# MAZ000159_-_Diagrama_el_ctrico.net
KiCad netlist of a schematic drawn in Altium Designer
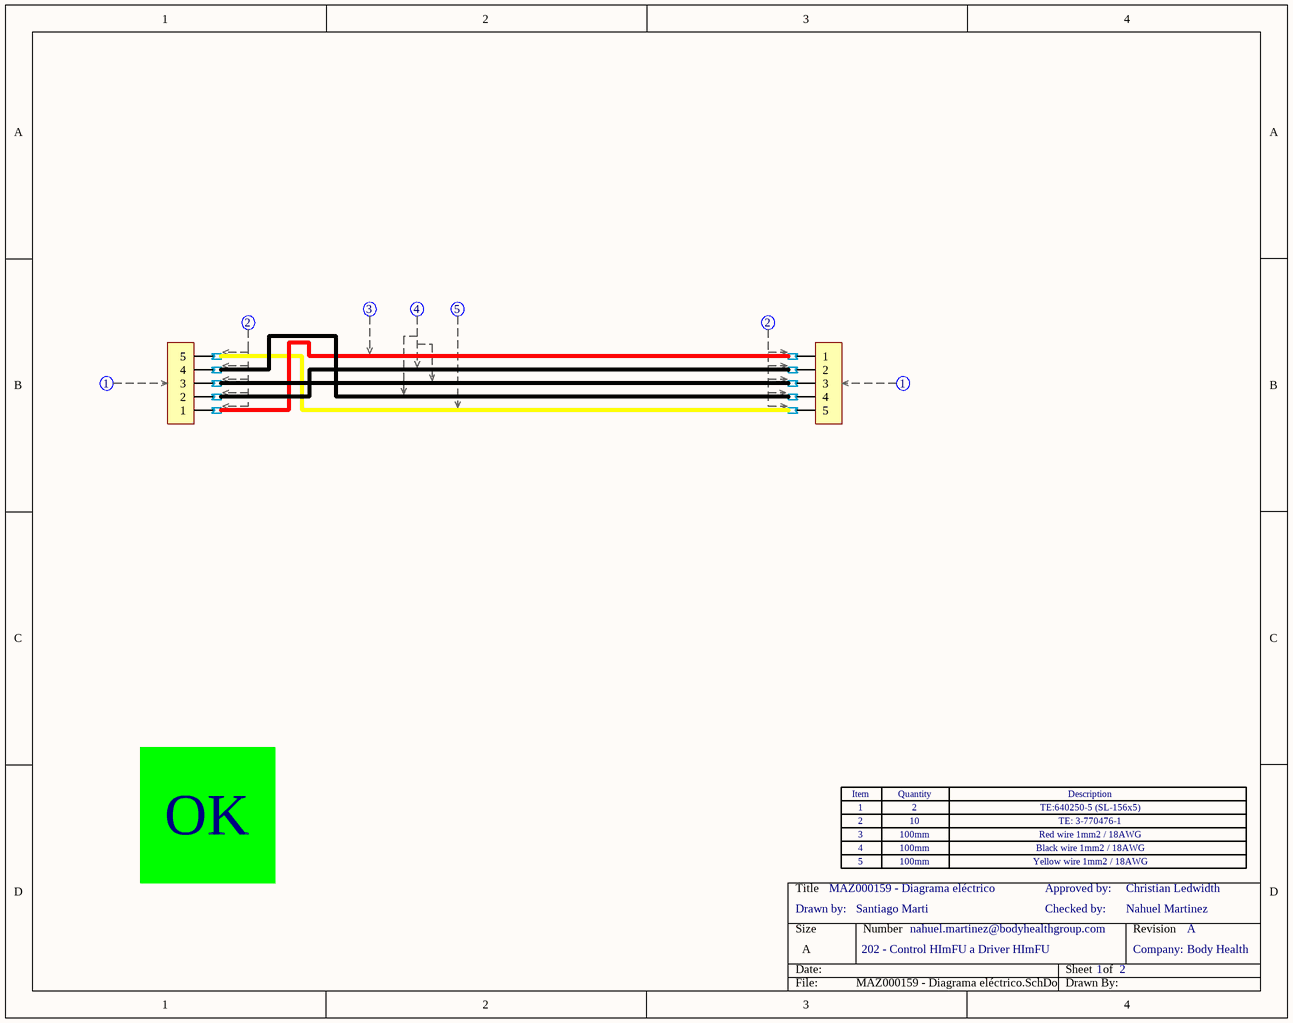
[diagram p0: MAZ000159 - Diagrama eléctrico.SchDoc]

(export (version "E")
  (design (tool "Eeschema 10.0.6"))
  (components
    (comp (ref "Con1")
      (value "SL156-5")
      (description "CONN RECEPT 5 POS W/RAMP SL-156")
      (libsource (lib "LibreriaParaPlanos") (part "SL156-5"))
    )
    (comp (ref "Con2")
      (value "SL156-5")
      (description "CONN RECEPT 5 POS W/RAMP SL-156")
      (libsource (lib "") (part "SL156-5_2"))
    )
    (comp (ref "Soc1")
      (value "sock_SL156_770476-1")
      (description "CONN SOCKET 18-24AWG CRIMP TIN")
      (libsource (lib "LibreriaParaPlanos") (part "sock_SL156_770476-1"))
    )
    (comp (ref "Soc2")
      (value "sock_SL156_770476-1")
      (description "CONN SOCKET 18-24AWG CRIMP TIN")
      (libsource (lib "LibreriaParaPlanos") (part "sock_SL156_770476-1"))
    )
    (comp (ref "Soc3")
      (value "sock_SL156_770476-1")
      (description "CONN SOCKET 18-24AWG CRIMP TIN")
      (libsource (lib "LibreriaParaPlanos") (part "sock_SL156_770476-1"))
    )
    (comp (ref "Soc4")
      (value "sock_SL156_770476-1")
      (description "CONN SOCKET 18-24AWG CRIMP TIN")
      (libsource (lib "LibreriaParaPlanos") (part "sock_SL156_770476-1"))
    )
    (comp (ref "Soc5")
      (value "sock_SL156_770476-1")
      (description "CONN SOCKET 18-24AWG CRIMP TIN")
      (libsource (lib "LibreriaParaPlanos") (part "sock_SL156_770476-1"))
    )
    (comp (ref "Soc6")
      (value "sock_SL156_770476-1")
      (description "CONN SOCKET 18-24AWG CRIMP TIN")
      (libsource (lib "LibreriaParaPlanos") (part "sock_SL156_770476-1"))
    )
    (comp (ref "Soc7")
      (value "sock_SL156_770476-1")
      (description "CONN SOCKET 18-24AWG CRIMP TIN")
      (libsource (lib "LibreriaParaPlanos") (part "sock_SL156_770476-1"))
    )
    (comp (ref "Soc8")
      (value "sock_SL156_770476-1")
      (description "CONN SOCKET 18-24AWG CRIMP TIN")
      (libsource (lib "LibreriaParaPlanos") (part "sock_SL156_770476-1"))
    )
    (comp (ref "Soc9")
      (value "sock_SL156_770476-1")
      (description "CONN SOCKET 18-24AWG CRIMP TIN")
      (libsource (lib "LibreriaParaPlanos") (part "sock_SL156_770476-1"))
    )
    (comp (ref "Soc10")
      (value "sock_SL156_770476-1")
      (description "CONN SOCKET 18-24AWG CRIMP TIN")
      (libsource (lib "LibreriaParaPlanos") (part "sock_SL156_770476-1"))
    )
    (comp (ref "Zoc1")
      (value "Zócalo_Header")
      (description "Header para el zócalo de referencias")
      (libsource (lib "LibreriaParaPlanos") (part "Zócalo_Header"))
    )
    (comp (ref "Zoc2")
      (value "Zócalo_Item")
      (description "Ítem para el zócalo de referencias")
      (libsource (lib "LibreriaParaPlanos") (part "Zócalo_Item"))
    )
    (comp (ref "Zoc3")
      (value "Zócalo_Item")
      (description "Ítem para el zócalo de referencias")
      (libsource (lib "LibreriaParaPlanos") (part "Zócalo_Item"))
    )
    (comp (ref "Zoc4")
      (value "Zócalo_Item")
      (description "Ítem para el zócalo de referencias")
      (libsource (lib "LibreriaParaPlanos") (part "Zócalo_Item"))
    )
    (comp (ref "Zoc5")
      (value "Zócalo_Item")
      (description "Ítem para el zócalo de referencias")
      (libsource (lib "LibreriaParaPlanos") (part "Zócalo_Item"))
    )
    (comp (ref "Zoc6")
      (value "Zócalo_Item")
      (description "Ítem para el zócalo de referencias")
      (libsource (lib "LibreriaParaPlanos") (part "Zócalo_Item"))
    )
  )
  (nets
    (net (code "1") (name "Net-(Con1-Pad1)") (class "Default")
      (node (ref "Con1") (pin "1") (pinfunction "1_1") (pintype "passive"))
      (node (ref "Soc9") (pin "0") (pinfunction "0_0") (pintype "passive"))
    )
    (net (code "2") (name "Net-(Con1-Pad2)") (class "Default")
      (node (ref "Con1") (pin "2") (pinfunction "2_2") (pintype "passive"))
      (node (ref "Soc7") (pin "0") (pinfunction "0_0") (pintype "passive"))
    )
    (net (code "3") (name "Net-(Con1-Pad3)") (class "Default")
      (node (ref "Con1") (pin "3") (pinfunction "3_3") (pintype "passive"))
      (node (ref "Soc5") (pin "0") (pinfunction "0_0") (pintype "passive"))
    )
    (net (code "4") (name "Net-(Con1-Pad4)") (class "Default")
      (node (ref "Con1") (pin "4") (pinfunction "4_4") (pintype "passive"))
      (node (ref "Soc3") (pin "0") (pinfunction "0_0") (pintype "passive"))
    )
    (net (code "5") (name "Net-(Con1-Pad5)") (class "Default")
      (node (ref "Con1") (pin "5") (pinfunction "5_5") (pintype "passive"))
      (node (ref "Soc1") (pin "0") (pinfunction "0_0") (pintype "passive"))
    )
    (net (code "6") (name "Net-(Con2-Pad1)") (class "Default")
      (node (ref "Con2") (pin "1") (pinfunction "1_1") (pintype "passive"))
      (node (ref "Soc2") (pin "0") (pinfunction "0_0") (pintype "passive"))
    )
    (net (code "7") (name "Net-(Con2-Pad2)") (class "Default")
      (node (ref "Con2") (pin "2") (pinfunction "2_2") (pintype "passive"))
      (node (ref "Soc4") (pin "0") (pinfunction "0_0") (pintype "passive"))
    )
    (net (code "8") (name "Net-(Con2-Pad3)") (class "Default")
      (node (ref "Con2") (pin "3") (pinfunction "3_3") (pintype "passive"))
      (node (ref "Soc6") (pin "0") (pinfunction "0_0") (pintype "passive"))
    )
    (net (code "9") (name "Net-(Con2-Pad4)") (class "Default")
      (node (ref "Con2") (pin "4") (pinfunction "4_4") (pintype "passive"))
      (node (ref "Soc8") (pin "0") (pinfunction "0_0") (pintype "passive"))
    )
    (net (code "10") (name "Net-(Con2-Pad5)") (class "Default")
      (node (ref "Con2") (pin "5") (pinfunction "5_5") (pintype "passive"))
      (node (ref "Soc10") (pin "0") (pinfunction "0_0") (pintype "passive"))
    )
    (net (code "11") (name "Net-(Soc1-Pad1)") (class "Default")
      (node (ref "Soc1") (pin "1") (pinfunction "1_1") (pintype "passive"))
      (node (ref "Soc10") (pin "1") (pinfunction "1_1") (pintype "passive"))
    )
    (net (code "12") (name "Net-(Soc2-Pad1)") (class "Default")
      (node (ref "Soc2") (pin "1") (pinfunction "1_1") (pintype "passive"))
      (node (ref "Soc9") (pin "1") (pinfunction "1_1") (pintype "passive"))
    )
    (net (code "13") (name "Net-(Soc3-Pad1)") (class "Default")
      (node (ref "Soc3") (pin "1") (pinfunction "1_1") (pintype "passive"))
      (node (ref "Soc8") (pin "1") (pinfunction "1_1") (pintype "passive"))
    )
    (net (code "14") (name "Net-(Soc4-Pad1)") (class "Default")
      (node (ref "Soc4") (pin "1") (pinfunction "1_1") (pintype "passive"))
      (node (ref "Soc7") (pin "1") (pinfunction "1_1") (pintype "passive"))
    )
    (net (code "15") (name "Net-(Soc5-Pad1)") (class "Default")
      (node (ref "Soc5") (pin "1") (pinfunction "1_1") (pintype "passive"))
      (node (ref "Soc6") (pin "1") (pinfunction "1_1") (pintype "passive"))
    )
  )
)
